# dj_midi_controller.net
KiCad netlist of a schematic drawn in EAGLE
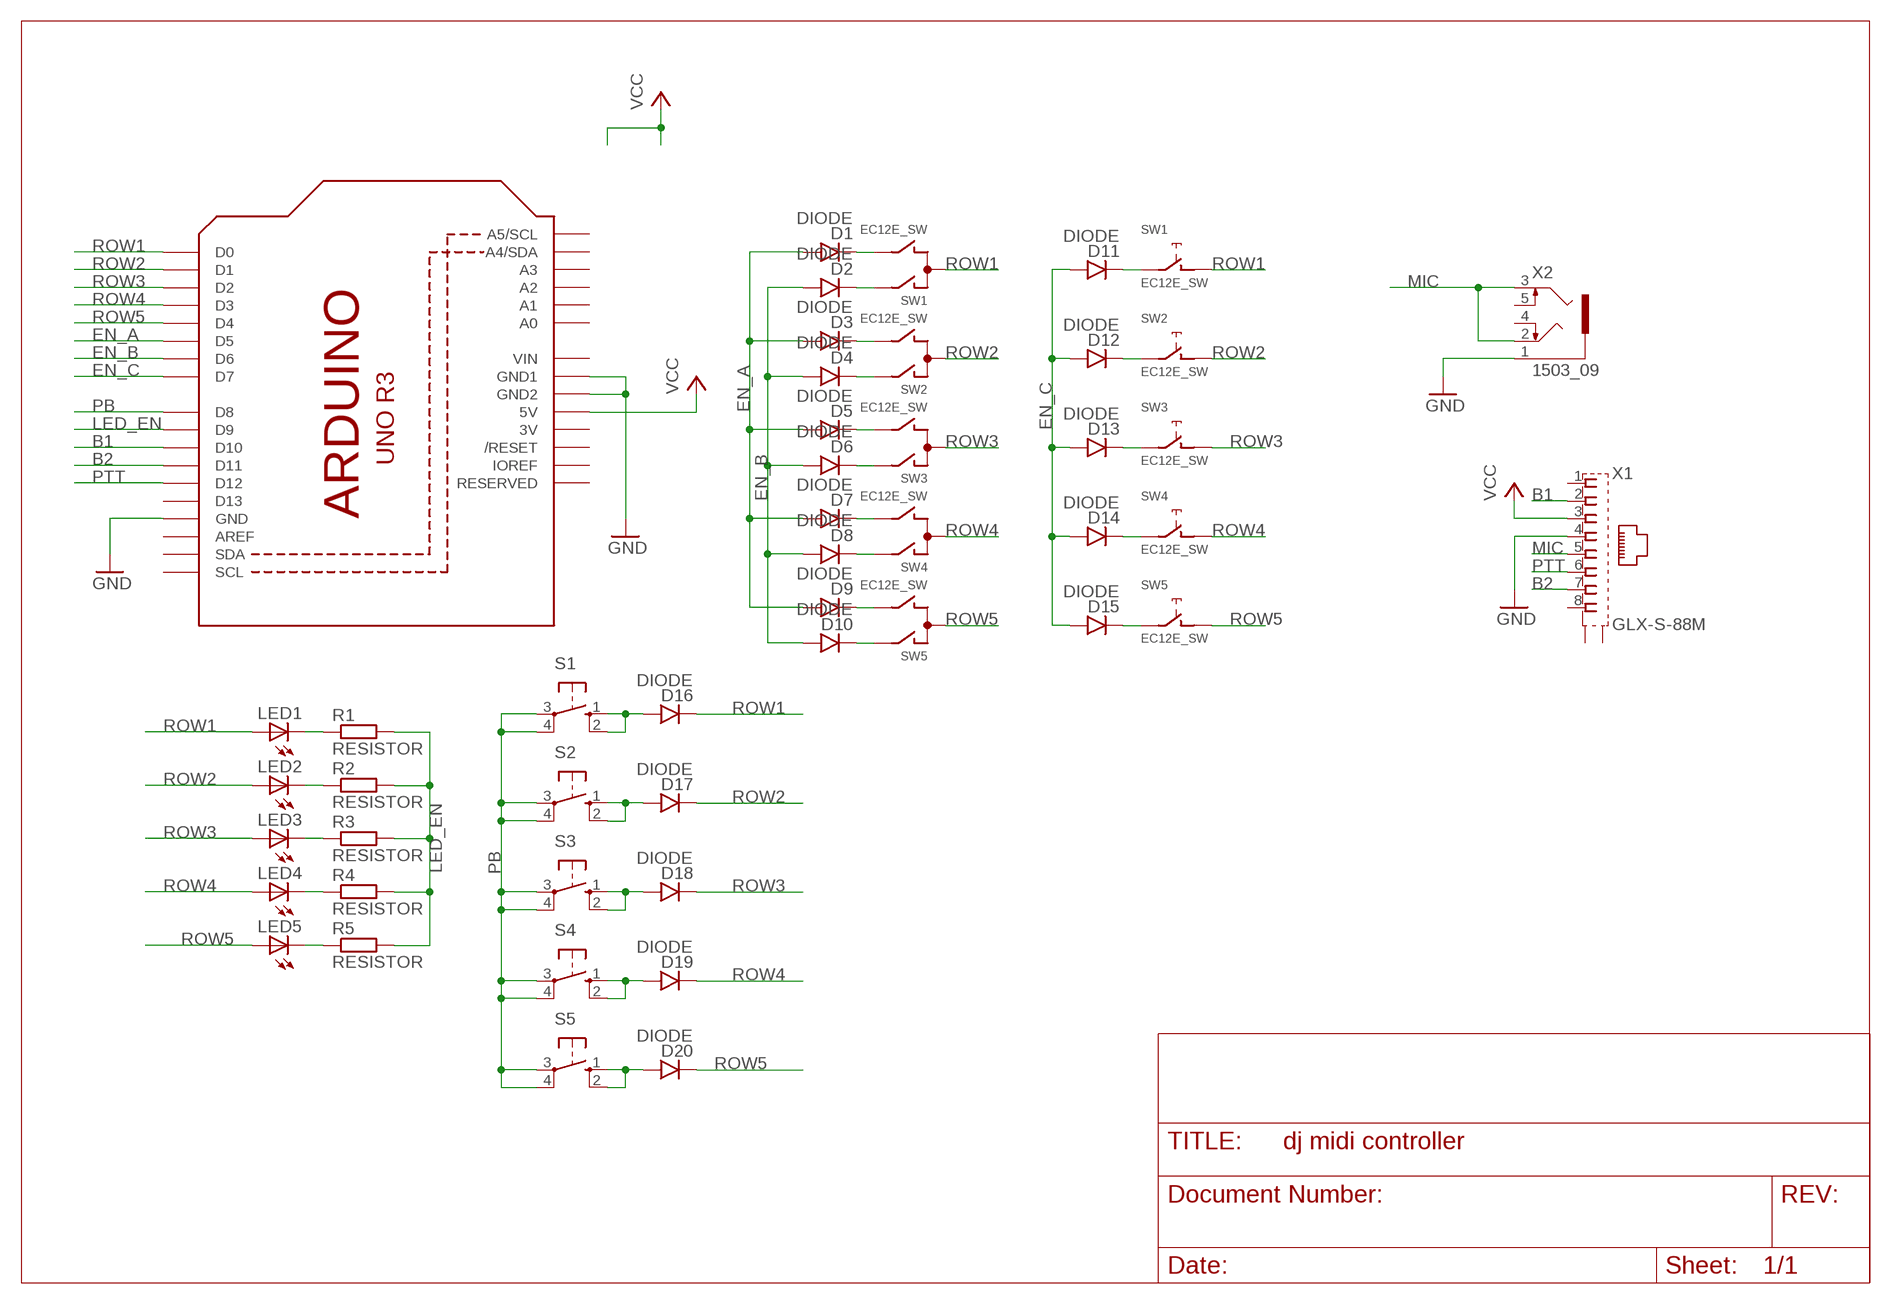
[diagram p0: schematic, sheet 1]

(export (version "E")
  (design (tool "Eeschema 10.0.6"))
  (components
    (comp (ref "D1")
      (value "DIODE")
      (footprint "eagle-import:M0805")
      (libsource (lib "eagle-import") (part "DIODE"))
    )
    (comp (ref "D2")
      (value "DIODE")
      (footprint "eagle-import:M0805")
      (libsource (lib "eagle-import") (part "DIODE"))
    )
    (comp (ref "D3")
      (value "DIODE")
      (footprint "eagle-import:M0805")
      (libsource (lib "eagle-import") (part "DIODE"))
    )
    (comp (ref "D4")
      (value "DIODE")
      (footprint "eagle-import:M0805")
      (libsource (lib "eagle-import") (part "DIODE"))
    )
    (comp (ref "D5")
      (value "DIODE")
      (footprint "eagle-import:M0805")
      (libsource (lib "eagle-import") (part "DIODE"))
    )
    (comp (ref "D6")
      (value "DIODE")
      (footprint "eagle-import:M0805")
      (libsource (lib "eagle-import") (part "DIODE"))
    )
    (comp (ref "D7")
      (value "DIODE")
      (footprint "eagle-import:M0805")
      (libsource (lib "eagle-import") (part "DIODE"))
    )
    (comp (ref "D8")
      (value "DIODE")
      (footprint "eagle-import:M0805")
      (libsource (lib "eagle-import") (part "DIODE"))
    )
    (comp (ref "D9")
      (value "DIODE")
      (footprint "eagle-import:M0805")
      (libsource (lib "eagle-import") (part "DIODE"))
    )
    (comp (ref "D10")
      (value "DIODE")
      (footprint "eagle-import:M0805")
      (libsource (lib "eagle-import") (part "DIODE"))
    )
    (comp (ref "D11")
      (value "DIODE")
      (footprint "eagle-import:M0805")
      (libsource (lib "eagle-import") (part "DIODE"))
    )
    (comp (ref "D12")
      (value "DIODE")
      (footprint "eagle-import:M0805")
      (libsource (lib "eagle-import") (part "DIODE"))
    )
    (comp (ref "D13")
      (value "DIODE")
      (footprint "eagle-import:M0805")
      (libsource (lib "eagle-import") (part "DIODE"))
    )
    (comp (ref "D14")
      (value "DIODE")
      (footprint "eagle-import:M0805")
      (libsource (lib "eagle-import") (part "DIODE"))
    )
    (comp (ref "D15")
      (value "DIODE")
      (footprint "eagle-import:M0805")
      (libsource (lib "eagle-import") (part "DIODE"))
    )
    (comp (ref "D16")
      (value "DIODE")
      (footprint "eagle-import:M0805")
      (libsource (lib "eagle-import") (part "DIODE"))
    )
    (comp (ref "D17")
      (value "DIODE")
      (footprint "eagle-import:M0805")
      (libsource (lib "eagle-import") (part "DIODE"))
    )
    (comp (ref "D18")
      (value "DIODE")
      (footprint "eagle-import:M0805")
      (libsource (lib "eagle-import") (part "DIODE"))
    )
    (comp (ref "D19")
      (value "DIODE")
      (footprint "eagle-import:M0805")
      (libsource (lib "eagle-import") (part "DIODE"))
    )
    (comp (ref "D20")
      (value "DIODE")
      (footprint "eagle-import:M0805")
      (libsource (lib "eagle-import") (part "DIODE"))
    )
    (comp (ref "LED1")
      (value "LED3MM")
      (footprint "eagle-import:LED3MM")
      (libsource (lib "eagle-import") (part "LED3MM"))
    )
    (comp (ref "LED2")
      (value "LED3MM")
      (footprint "eagle-import:LED3MM")
      (libsource (lib "eagle-import") (part "LED3MM"))
    )
    (comp (ref "LED3")
      (value "LED3MM")
      (footprint "eagle-import:LED3MM")
      (libsource (lib "eagle-import") (part "LED3MM"))
    )
    (comp (ref "LED4")
      (value "LED3MM")
      (footprint "eagle-import:LED3MM")
      (libsource (lib "eagle-import") (part "LED3MM"))
    )
    (comp (ref "LED5")
      (value "LED3MM")
      (footprint "eagle-import:LED3MM")
      (libsource (lib "eagle-import") (part "LED3MM"))
    )
    (comp (ref "R1")
      (value "RESISTOR")
      (footprint "eagle-import:M0805")
      (libsource (lib "eagle-import") (part "RESISTOR"))
    )
    (comp (ref "R2")
      (value "RESISTOR")
      (footprint "eagle-import:M0805")
      (libsource (lib "eagle-import") (part "RESISTOR"))
    )
    (comp (ref "R3")
      (value "RESISTOR")
      (footprint "eagle-import:M0805")
      (libsource (lib "eagle-import") (part "RESISTOR"))
    )
    (comp (ref "R4")
      (value "RESISTOR")
      (footprint "eagle-import:M0805")
      (libsource (lib "eagle-import") (part "RESISTOR"))
    )
    (comp (ref "R5")
      (value "RESISTOR")
      (footprint "eagle-import:M0805")
      (libsource (lib "eagle-import") (part "RESISTOR"))
    )
    (comp (ref "S1")
      (value "10-XX")
      (footprint "eagle-import:B3F-10XX")
      (fields (field (name "MPN") "B3F-1000"))
      (libsource (lib "eagle-import") (part "10-XX"))
    )
    (comp (ref "S2")
      (value "10-XX")
      (footprint "eagle-import:B3F-10XX")
      (fields (field (name "MPN") "B3F-1000"))
      (libsource (lib "eagle-import") (part "10-XX"))
    )
    (comp (ref "S3")
      (value "10-XX")
      (footprint "eagle-import:B3F-10XX")
      (fields (field (name "MPN") "B3F-1000"))
      (libsource (lib "eagle-import") (part "10-XX"))
    )
    (comp (ref "S4")
      (value "10-XX")
      (footprint "eagle-import:B3F-10XX")
      (fields (field (name "MPN") "B3F-1000"))
      (libsource (lib "eagle-import") (part "10-XX"))
    )
    (comp (ref "S5")
      (value "10-XX")
      (footprint "eagle-import:B3F-10XX")
      (fields (field (name "MPN") "B3F-1000"))
      (libsource (lib "eagle-import") (part "10-XX"))
    )
    (comp (ref "SW1")
      (value "EC12E_SW")
      (footprint "eagle-import:ALPS_EC12E_SW")
      (fields (field (name "MPN") "EC12E2424407"))
      (libsource (lib "eagle-import") (part "EC12E_SW"))
    )
    (comp (ref "SW2")
      (value "EC12E_SW")
      (footprint "eagle-import:ALPS_EC12E_SW")
      (fields (field (name "MPN") "EC12E2424407"))
      (libsource (lib "eagle-import") (part "EC12E_SW"))
    )
    (comp (ref "SW3")
      (value "EC12E_SW")
      (footprint "eagle-import:ALPS_EC12E_SW")
      (fields (field (name "MPN") "EC12E2424407"))
      (libsource (lib "eagle-import") (part "EC12E_SW"))
    )
    (comp (ref "SW4")
      (value "EC12E_SW")
      (footprint "eagle-import:ALPS_EC12E_SW")
      (fields (field (name "MPN") "EC12E2424407"))
      (libsource (lib "eagle-import") (part "EC12E_SW"))
    )
    (comp (ref "SW5")
      (value "EC12E_SW")
      (footprint "eagle-import:ALPS_EC12E_SW")
      (fields (field (name "MPN") "EC12E2424407"))
      (libsource (lib "eagle-import") (part "EC12E_SW"))
    )
    (comp (ref "U2")
      (value "ARDUINOR3-DIMENSION")
      (footprint "eagle-import:ARDUINOR3")
      (libsource (lib "eagle-import") (part "ARDUINOR3-DIMENSION"))
    )
    (comp (ref "X1")
      (value "GLX-S-88M")
      (footprint "eagle-import:GLX-S-88M")
      (libsource (lib "eagle-import") (part "GLX-S-88M"))
    )
    (comp (ref "X2")
      (value "1503_09")
      (footprint "eagle-import:1503_09")
      (libsource (lib "eagle-import") (part "1503_09"))
    )
  )
  (nets
    (net (code "1") (name "/3V") (class "Default")
      (node (ref "U2") (pin "3V") (pinfunction "3V_3V") (pintype "power_in"))
    )
    (net (code "2") (name "/B1") (class "Default")
      (node (ref "U2") (pin "D10") (pinfunction "D10_D10") (pintype "bidirectional"))
      (node (ref "X1") (pin "2") (pinfunction "2_2") (pintype "passive"))
    )
    (net (code "3") (name "/B2") (class "Default")
      (node (ref "U2") (pin "D11") (pinfunction "D11_D11") (pintype "bidirectional"))
      (node (ref "X1") (pin "7") (pinfunction "7_7") (pintype "passive"))
    )
    (net (code "4") (name "/EN_A") (class "Default")
      (node (ref "D1") (pin "1") (pinfunction "A_1") (pintype "passive"))
      (node (ref "D3") (pin "1") (pinfunction "A_1") (pintype "passive"))
      (node (ref "D5") (pin "1") (pinfunction "A_1") (pintype "passive"))
      (node (ref "D7") (pin "1") (pinfunction "A_1") (pintype "passive"))
      (node (ref "D9") (pin "1") (pinfunction "A_1") (pintype "passive"))
      (node (ref "U2") (pin "D5") (pinfunction "D5_D5") (pintype "bidirectional"))
    )
    (net (code "5") (name "/EN_B") (class "Default")
      (node (ref "D10") (pin "1") (pinfunction "A_1") (pintype "passive"))
      (node (ref "D2") (pin "1") (pinfunction "A_1") (pintype "passive"))
      (node (ref "D4") (pin "1") (pinfunction "A_1") (pintype "passive"))
      (node (ref "D6") (pin "1") (pinfunction "A_1") (pintype "passive"))
      (node (ref "D8") (pin "1") (pinfunction "A_1") (pintype "passive"))
      (node (ref "U2") (pin "D6") (pinfunction "D6_D6") (pintype "bidirectional"))
    )
    (net (code "6") (name "/EN_C") (class "Default")
      (node (ref "D11") (pin "1") (pinfunction "A_1") (pintype "passive"))
      (node (ref "D12") (pin "1") (pinfunction "A_1") (pintype "passive"))
      (node (ref "D13") (pin "1") (pinfunction "A_1") (pintype "passive"))
      (node (ref "D14") (pin "1") (pinfunction "A_1") (pintype "passive"))
      (node (ref "D15") (pin "1") (pinfunction "A_1") (pintype "passive"))
      (node (ref "U2") (pin "D7") (pinfunction "D7_D7") (pintype "bidirectional"))
    )
    (net (code "7") (name "/LED_EN") (class "Default")
      (node (ref "R1") (pin "2") (pinfunction "2_2") (pintype "passive"))
      (node (ref "R2") (pin "2") (pinfunction "2_2") (pintype "passive"))
      (node (ref "R3") (pin "2") (pinfunction "2_2") (pintype "passive"))
      (node (ref "R4") (pin "2") (pinfunction "2_2") (pintype "passive"))
      (node (ref "R5") (pin "2") (pinfunction "2_2") (pintype "passive"))
      (node (ref "U2") (pin "D9") (pinfunction "D9_D9") (pintype "bidirectional"))
    )
    (net (code "8") (name "/MIC") (class "Default")
      (node (ref "X1") (pin "5") (pinfunction "5_5") (pintype "passive"))
      (node (ref "X2") (pin "2") (pinfunction "2_2") (pintype "passive"))
      (node (ref "X2") (pin "3") (pinfunction "3_3") (pintype "passive"))
    )
    (net (code "9") (name "/PB") (class "Default")
      (node (ref "S1") (pin "3") (pinfunction "P_3") (pintype "passive"))
      (node (ref "S1") (pin "4") (pinfunction "P1_4") (pintype "passive"))
      (node (ref "S2") (pin "3") (pinfunction "P_3") (pintype "passive"))
      (node (ref "S2") (pin "4") (pinfunction "P1_4") (pintype "passive"))
      (node (ref "S3") (pin "3") (pinfunction "P_3") (pintype "passive"))
      (node (ref "S3") (pin "4") (pinfunction "P1_4") (pintype "passive"))
      (node (ref "S4") (pin "3") (pinfunction "P_3") (pintype "passive"))
      (node (ref "S4") (pin "4") (pinfunction "P1_4") (pintype "passive"))
      (node (ref "S5") (pin "3") (pinfunction "P_3") (pintype "passive"))
      (node (ref "S5") (pin "4") (pinfunction "P1_4") (pintype "passive"))
      (node (ref "U2") (pin "D8") (pinfunction "D8_D8") (pintype "bidirectional"))
    )
    (net (code "10") (name "/PTT") (class "Default")
      (node (ref "U2") (pin "D12") (pinfunction "D12_D12") (pintype "bidirectional"))
      (node (ref "X1") (pin "6") (pinfunction "6_6") (pintype "passive"))
    )
    (net (code "11") (name "/ROW1") (class "Default")
      (node (ref "D16") (pin "2") (pinfunction "C_2") (pintype "passive"))
      (node (ref "LED1") (pin "A") (pinfunction "A_A") (pintype "passive"))
      (node (ref "SW1") (pin "C") (pinfunction "C_C") (pintype "passive"))
      (node (ref "SW1") (pin "D") (pinfunction "1_D") (pintype "passive"))
      (node (ref "U2") (pin "D0") (pinfunction "D0_D0") (pintype "bidirectional"))
    )
    (net (code "12") (name "/ROW2") (class "Default")
      (node (ref "D17") (pin "2") (pinfunction "C_2") (pintype "passive"))
      (node (ref "LED2") (pin "A") (pinfunction "A_A") (pintype "passive"))
      (node (ref "SW2") (pin "C") (pinfunction "C_C") (pintype "passive"))
      (node (ref "SW2") (pin "D") (pinfunction "1_D") (pintype "passive"))
      (node (ref "U2") (pin "D1") (pinfunction "D1_D1") (pintype "bidirectional"))
    )
    (net (code "13") (name "/ROW3") (class "Default")
      (node (ref "D18") (pin "2") (pinfunction "C_2") (pintype "passive"))
      (node (ref "LED3") (pin "A") (pinfunction "A_A") (pintype "passive"))
      (node (ref "SW3") (pin "C") (pinfunction "C_C") (pintype "passive"))
      (node (ref "SW3") (pin "D") (pinfunction "1_D") (pintype "passive"))
      (node (ref "U2") (pin "D2") (pinfunction "D2_D2") (pintype "bidirectional"))
    )
    (net (code "14") (name "/ROW4") (class "Default")
      (node (ref "D19") (pin "2") (pinfunction "C_2") (pintype "passive"))
      (node (ref "LED4") (pin "A") (pinfunction "A_A") (pintype "passive"))
      (node (ref "SW4") (pin "C") (pinfunction "C_C") (pintype "passive"))
      (node (ref "SW4") (pin "D") (pinfunction "1_D") (pintype "passive"))
      (node (ref "U2") (pin "D3") (pinfunction "D3_D3") (pintype "bidirectional"))
    )
    (net (code "15") (name "/ROW5") (class "Default")
      (node (ref "D20") (pin "2") (pinfunction "C_2") (pintype "passive"))
      (node (ref "LED5") (pin "A") (pinfunction "A_A") (pintype "passive"))
      (node (ref "SW5") (pin "C") (pinfunction "C_C") (pintype "passive"))
      (node (ref "SW5") (pin "D") (pinfunction "1_D") (pintype "passive"))
      (node (ref "U2") (pin "D4") (pinfunction "D4_D4") (pintype "bidirectional"))
    )
    (net (code "16") (name "/VIN") (class "Default")
      (node (ref "U2") (pin "VIN") (pinfunction "VIN_VIN") (pintype "power_in"))
    )
    (net (code "17") (name "GND") (class "Default")
      (node (ref "U2") (pin "GND") (pinfunction "GND_GND") (pintype "power_in"))
      (node (ref "U2") (pin "GND1") (pinfunction "GND1_GND1") (pintype "power_in"))
      (node (ref "U2") (pin "GND2") (pinfunction "GND2_GND2") (pintype "power_in"))
      (node (ref "X1") (pin "4") (pinfunction "4_4") (pintype "passive"))
      (node (ref "X2") (pin "1") (pinfunction "1_1") (pintype "passive"))
    )
    (net (code "18") (name "Net-(D1-C)") (class "Default")
      (node (ref "D1") (pin "2") (pinfunction "C_2") (pintype "passive"))
      (node (ref "SW1") (pin "B") (pinfunction "B_B") (pintype "passive"))
    )
    (net (code "19") (name "Net-(D2-C)") (class "Default")
      (node (ref "D2") (pin "2") (pinfunction "C_2") (pintype "passive"))
      (node (ref "SW1") (pin "A") (pinfunction "A_A") (pintype "passive"))
    )
    (net (code "20") (name "Net-(D3-C)") (class "Default")
      (node (ref "D3") (pin "2") (pinfunction "C_2") (pintype "passive"))
      (node (ref "SW2") (pin "B") (pinfunction "B_B") (pintype "passive"))
    )
    (net (code "21") (name "Net-(D4-C)") (class "Default")
      (node (ref "D4") (pin "2") (pinfunction "C_2") (pintype "passive"))
      (node (ref "SW2") (pin "A") (pinfunction "A_A") (pintype "passive"))
    )
    (net (code "22") (name "Net-(D5-C)") (class "Default")
      (node (ref "D5") (pin "2") (pinfunction "C_2") (pintype "passive"))
      (node (ref "SW3") (pin "B") (pinfunction "B_B") (pintype "passive"))
    )
    (net (code "23") (name "Net-(D6-C)") (class "Default")
      (node (ref "D6") (pin "2") (pinfunction "C_2") (pintype "passive"))
      (node (ref "SW3") (pin "A") (pinfunction "A_A") (pintype "passive"))
    )
    (net (code "24") (name "Net-(D7-C)") (class "Default")
      (node (ref "D7") (pin "2") (pinfunction "C_2") (pintype "passive"))
      (node (ref "SW4") (pin "B") (pinfunction "B_B") (pintype "passive"))
    )
    (net (code "25") (name "Net-(D8-C)") (class "Default")
      (node (ref "D8") (pin "2") (pinfunction "C_2") (pintype "passive"))
      (node (ref "SW4") (pin "A") (pinfunction "A_A") (pintype "passive"))
    )
    (net (code "26") (name "Net-(D9-C)") (class "Default")
      (node (ref "D9") (pin "2") (pinfunction "C_2") (pintype "passive"))
      (node (ref "SW5") (pin "B") (pinfunction "B_B") (pintype "passive"))
    )
    (net (code "27") (name "Net-(D10-C)") (class "Default")
      (node (ref "D10") (pin "2") (pinfunction "C_2") (pintype "passive"))
      (node (ref "SW5") (pin "A") (pinfunction "A_A") (pintype "passive"))
    )
    (net (code "28") (name "Net-(D11-C)") (class "Default")
      (node (ref "D11") (pin "2") (pinfunction "C_2") (pintype "passive"))
      (node (ref "SW1") (pin "E") (pinfunction "2_E") (pintype "passive"))
    )
    (net (code "29") (name "Net-(D12-C)") (class "Default")
      (node (ref "D12") (pin "2") (pinfunction "C_2") (pintype "passive"))
      (node (ref "SW2") (pin "E") (pinfunction "2_E") (pintype "passive"))
    )
    (net (code "30") (name "Net-(D13-C)") (class "Default")
      (node (ref "D13") (pin "2") (pinfunction "C_2") (pintype "passive"))
      (node (ref "SW3") (pin "E") (pinfunction "2_E") (pintype "passive"))
    )
    (net (code "31") (name "Net-(D14-C)") (class "Default")
      (node (ref "D14") (pin "2") (pinfunction "C_2") (pintype "passive"))
      (node (ref "SW4") (pin "E") (pinfunction "2_E") (pintype "passive"))
    )
    (net (code "32") (name "Net-(D15-C)") (class "Default")
      (node (ref "D15") (pin "2") (pinfunction "C_2") (pintype "passive"))
      (node (ref "SW5") (pin "E") (pinfunction "2_E") (pintype "passive"))
    )
    (net (code "33") (name "Net-(D16-A)") (class "Default")
      (node (ref "D16") (pin "1") (pinfunction "A_1") (pintype "passive"))
      (node (ref "S1") (pin "1") (pinfunction "S_1") (pintype "passive"))
      (node (ref "S1") (pin "2") (pinfunction "S1_2") (pintype "passive"))
    )
    (net (code "34") (name "Net-(D17-A)") (class "Default")
      (node (ref "D17") (pin "1") (pinfunction "A_1") (pintype "passive"))
      (node (ref "S2") (pin "1") (pinfunction "S_1") (pintype "passive"))
      (node (ref "S2") (pin "2") (pinfunction "S1_2") (pintype "passive"))
    )
    (net (code "35") (name "Net-(D18-A)") (class "Default")
      (node (ref "D18") (pin "1") (pinfunction "A_1") (pintype "passive"))
      (node (ref "S3") (pin "1") (pinfunction "S_1") (pintype "passive"))
      (node (ref "S3") (pin "2") (pinfunction "S1_2") (pintype "passive"))
    )
    (net (code "36") (name "Net-(D19-A)") (class "Default")
      (node (ref "D19") (pin "1") (pinfunction "A_1") (pintype "passive"))
      (node (ref "S4") (pin "1") (pinfunction "S_1") (pintype "passive"))
      (node (ref "S4") (pin "2") (pinfunction "S1_2") (pintype "passive"))
    )
    (net (code "37") (name "Net-(D20-A)") (class "Default")
      (node (ref "D20") (pin "1") (pinfunction "A_1") (pintype "passive"))
      (node (ref "S5") (pin "1") (pinfunction "S_1") (pintype "passive"))
      (node (ref "S5") (pin "2") (pinfunction "S1_2") (pintype "passive"))
    )
    (net (code "38") (name "Net-(LED1-C)") (class "Default")
      (node (ref "LED1") (pin "K") (pinfunction "C_K") (pintype "passive"))
      (node (ref "R1") (pin "1") (pinfunction "1_1") (pintype "passive"))
    )
    (net (code "39") (name "Net-(LED2-C)") (class "Default")
      (node (ref "LED2") (pin "K") (pinfunction "C_K") (pintype "passive"))
      (node (ref "R2") (pin "1") (pinfunction "1_1") (pintype "passive"))
    )
    (net (code "40") (name "Net-(LED3-C)") (class "Default")
      (node (ref "LED3") (pin "K") (pinfunction "C_K") (pintype "passive"))
      (node (ref "R3") (pin "1") (pinfunction "1_1") (pintype "passive"))
    )
    (net (code "41") (name "Net-(LED4-C)") (class "Default")
      (node (ref "LED4") (pin "K") (pinfunction "C_K") (pintype "passive"))
      (node (ref "R4") (pin "1") (pinfunction "1_1") (pintype "passive"))
    )
    (net (code "42") (name "Net-(LED5-C)") (class "Default")
      (node (ref "LED5") (pin "K") (pinfunction "C_K") (pintype "passive"))
      (node (ref "R5") (pin "1") (pinfunction "1_1") (pintype "passive"))
    )
    (net (code "43") (name "VCC") (class "Default")
      (node (ref "U2") (pin "5V") (pinfunction "5V_5V") (pintype "power_in"))
      (node (ref "X1") (pin "3") (pinfunction "3_3") (pintype "passive"))
    )
    (net (code "44") (name "unconnected-(U2-A4{slash}SDA-PadA4)") (class "Default")
      (node (ref "U2") (pin "A4") (pinfunction "A4/SDA_A4") (pintype "bidirectional"))
    )
    (net (code "45") (name "unconnected-(U2-A5{slash}SCL-PadA5)") (class "Default")
      (node (ref "U2") (pin "A5") (pinfunction "A5/SCL_A5") (pintype "bidirectional"))
    )
    (net (code "46") (name "unconnected-(U2-PadA0)") (class "Default")
      (node (ref "U2") (pin "A0") (pinfunction "A0_A0") (pintype "bidirectional"))
    )
    (net (code "47") (name "unconnected-(U2-PadA1)") (class "Default")
      (node (ref "U2") (pin "A1") (pinfunction "A1_A1") (pintype "bidirectional"))
    )
    (net (code "48") (name "unconnected-(U2-PadA2)") (class "Default")
      (node (ref "U2") (pin "A2") (pinfunction "A2_A2") (pintype "bidirectional"))
    )
    (net (code "49") (name "unconnected-(U2-PadA3)") (class "Default")
      (node (ref "U2") (pin "A3") (pinfunction "A3_A3") (pintype "bidirectional"))
    )
    (net (code "50") (name "unconnected-(U2-PadAREF)") (class "Default")
      (node (ref "U2") (pin "AREF") (pinfunction "AREF_AREF") (pintype "bidirectional"))
    )
    (net (code "51") (name "unconnected-(U2-PadD13)") (class "Default")
      (node (ref "U2") (pin "D13") (pinfunction "D13_D13") (pintype "bidirectional"))
    )
    (net (code "52") (name "unconnected-(U2-PadIOREF)") (class "Default")
      (node (ref "U2") (pin "IOREF") (pinfunction "IOREF_IOREF") (pintype "output"))
    )
    (net (code "53") (name "unconnected-(U2-PadRESERVED)") (class "Default")
      (node (ref "U2") (pin "RESERVED") (pinfunction "RESERVED_RESERVED") (pintype "no_connect"))
    )
    (net (code "54") (name "unconnected-(U2-PadSCL)") (class "Default")
      (node (ref "U2") (pin "SCL") (pinfunction "SCL_SCL") (pintype "bidirectional"))
    )
    (net (code "55") (name "unconnected-(U2-PadSDA)") (class "Default")
      (node (ref "U2") (pin "SDA") (pinfunction "SDA_SDA") (pintype "bidirectional"))
    )
    (net (code "56") (name "unconnected-(U2-{slash}RESET-PadRESET)") (class "Default")
      (node (ref "U2") (pin "RESET") (pinfunction "/RESET_RESET") (pintype "bidirectional"))
    )
    (net (code "57") (name "unconnected-(X1-Pad1)") (class "Default")
      (node (ref "X1") (pin "1") (pinfunction "1_1") (pintype "passive"))
    )
    (net (code "58") (name "unconnected-(X1-Pad8)") (class "Default")
      (node (ref "X1") (pin "8") (pinfunction "8_8") (pintype "passive"))
    )
    (net (code "59") (name "unconnected-(X1-PadS1)") (class "Default")
      (node (ref "X1") (pin "S1") (pinfunction "S1_S1") (pintype "passive"))
    )
    (net (code "60") (name "unconnected-(X1-PadS2)") (class "Default")
      (node (ref "X1") (pin "S2") (pinfunction "S2_S2") (pintype "passive"))
    )
    (net (code "61") (name "unconnected-(X2-Pad4)") (class "Default")
      (node (ref "X2") (pin "4") (pinfunction "4_4") (pintype "passive"))
    )
    (net (code "62") (name "unconnected-(X2-Pad5)") (class "Default")
      (node (ref "X2") (pin "5") (pinfunction "5_5") (pintype "passive"))
    )
  )
)
